# NucleoShield.net
KiCad netlist of a schematic drawn in EAGLE
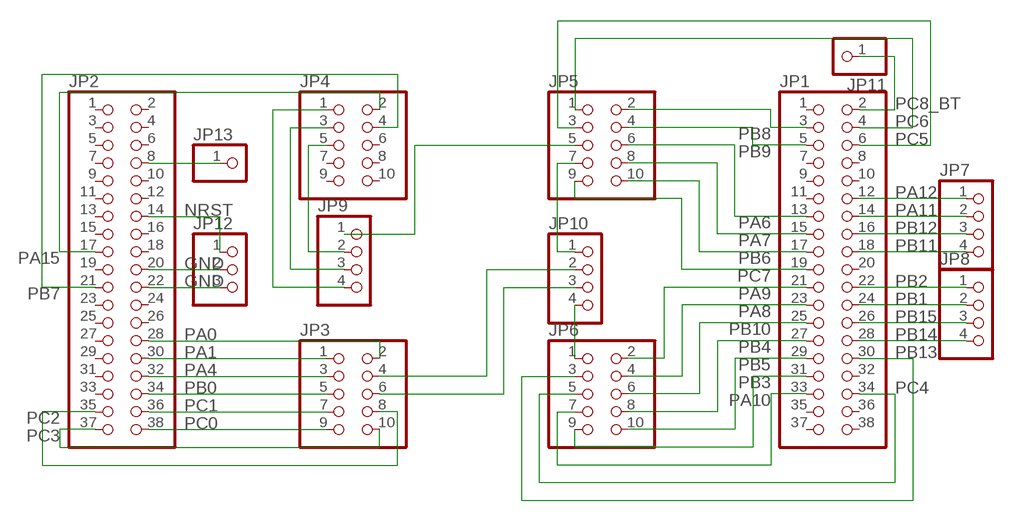
[diagram p0: schematic, sheet 1]

(export (version "E")
  (design (tool "Eeschema 10.0.6"))
  (components
    (comp (ref "JP1")
      (value "PINHD-2X19")
      (footprint "eagle-import:2X19")
      (libsource (lib "eagle-import") (part "PINHD-2X19"))
    )
    (comp (ref "JP2")
      (value "PINHD-2X19")
      (footprint "eagle-import:2X19")
      (libsource (lib "eagle-import") (part "PINHD-2X19"))
    )
    (comp (ref "JP3")
      (value "PINHD-2X5")
      (footprint "eagle-import:2X05")
      (libsource (lib "eagle-import") (part "PINHD-2X5"))
    )
    (comp (ref "JP4")
      (value "PINHD-2X5")
      (footprint "eagle-import:2X05")
      (libsource (lib "eagle-import") (part "PINHD-2X5"))
    )
    (comp (ref "JP5")
      (value "PINHD-2X5")
      (footprint "eagle-import:2X05")
      (libsource (lib "eagle-import") (part "PINHD-2X5"))
    )
    (comp (ref "JP6")
      (value "PINHD-2X5")
      (footprint "eagle-import:2X05")
      (libsource (lib "eagle-import") (part "PINHD-2X5"))
    )
    (comp (ref "JP7")
      (value "PINHD-1X4")
      (footprint "eagle-import:1X04")
      (libsource (lib "eagle-import") (part "PINHD-1X4"))
    )
    (comp (ref "JP8")
      (value "PINHD-1X4")
      (footprint "eagle-import:1X04")
      (libsource (lib "eagle-import") (part "PINHD-1X4"))
    )
    (comp (ref "JP9")
      (value "PINHD-1X4")
      (footprint "eagle-import:1X04")
      (libsource (lib "eagle-import") (part "PINHD-1X4"))
    )
    (comp (ref "JP10")
      (value "PINHD-1X4")
      (footprint "eagle-import:1X04")
      (libsource (lib "eagle-import") (part "PINHD-1X4"))
    )
    (comp (ref "JP11")
      (value "PINHD-1X1")
      (footprint "eagle-import:1X01")
      (libsource (lib "eagle-import") (part "PINHD-1X1"))
    )
    (comp (ref "JP12")
      (value "PINHD-1X3")
      (footprint "eagle-import:1X03")
      (libsource (lib "eagle-import") (part "PINHD-1X3"))
    )
    (comp (ref "JP13")
      (value "PINHD-1X1")
      (footprint "eagle-import:1X01")
      (libsource (lib "eagle-import") (part "PINHD-1X1"))
    )
  )
  (nets
    (net (code "1") (name "/GND") (class "Default")
      (node (ref "JP12") (pin "2") (pinfunction "2_2") (pintype "passive"))
      (node (ref "JP12") (pin "3") (pinfunction "3_3") (pintype "passive"))
      (node (ref "JP2") (pin "20") (pinfunction "20_20") (pintype "passive"))
      (node (ref "JP2") (pin "22") (pinfunction "22_22") (pintype "passive"))
    )
    (net (code "2") (name "/NRST") (class "Default")
      (node (ref "JP12") (pin "1") (pinfunction "1_1") (pintype "passive"))
      (node (ref "JP2") (pin "14") (pinfunction "14_14") (pintype "passive"))
    )
    (net (code "3") (name "/PA0") (class "Default")
      (node (ref "JP2") (pin "28") (pinfunction "28_28") (pintype "passive"))
      (node (ref "JP3") (pin "2") (pinfunction "2_2") (pintype "passive"))
    )
    (net (code "4") (name "/PA1") (class "Default")
      (node (ref "JP2") (pin "30") (pinfunction "30_30") (pintype "passive"))
      (node (ref "JP3") (pin "1") (pinfunction "1_1") (pintype "passive"))
    )
    (net (code "5") (name "/PA4") (class "Default")
      (node (ref "JP2") (pin "32") (pinfunction "32_32") (pintype "passive"))
      (node (ref "JP3") (pin "3") (pinfunction "3_3") (pintype "passive"))
    )
    (net (code "6") (name "/PA6") (class "Default")
      (node (ref "JP1") (pin "13") (pinfunction "13_13") (pintype "passive"))
      (node (ref "JP5") (pin "6") (pinfunction "6_6") (pintype "passive"))
    )
    (net (code "7") (name "/PA7") (class "Default")
      (node (ref "JP1") (pin "15") (pinfunction "15_15") (pintype "passive"))
      (node (ref "JP5") (pin "8") (pinfunction "8_8") (pintype "passive"))
    )
    (net (code "8") (name "/PA8") (class "Default")
      (node (ref "JP1") (pin "23") (pinfunction "23_23") (pintype "passive"))
      (node (ref "JP6") (pin "4") (pinfunction "4_4") (pintype "passive"))
    )
    (net (code "9") (name "/PA9") (class "Default")
      (node (ref "JP1") (pin "21") (pinfunction "21_21") (pintype "passive"))
      (node (ref "JP6") (pin "2") (pinfunction "2_2") (pintype "passive"))
    )
    (net (code "10") (name "/PA10") (class "Default")
      (node (ref "JP1") (pin "33") (pinfunction "33_33") (pintype "passive"))
      (node (ref "JP6") (pin "7") (pinfunction "7_7") (pintype "passive"))
    )
    (net (code "11") (name "/PA11") (class "Default")
      (node (ref "JP1") (pin "14") (pinfunction "14_14") (pintype "passive"))
      (node (ref "JP7") (pin "2") (pinfunction "2_2") (pintype "passive"))
    )
    (net (code "12") (name "/PA12") (class "Default")
      (node (ref "JP1") (pin "12") (pinfunction "12_12") (pintype "passive"))
      (node (ref "JP7") (pin "1") (pinfunction "1_1") (pintype "passive"))
    )
    (net (code "13") (name "/PA15") (class "Default")
      (node (ref "JP2") (pin "17") (pinfunction "17_17") (pintype "passive"))
      (node (ref "JP4") (pin "2") (pinfunction "2_2") (pintype "passive"))
    )
    (net (code "14") (name "/PB0") (class "Default")
      (node (ref "JP2") (pin "34") (pinfunction "34_34") (pintype "passive"))
      (node (ref "JP3") (pin "5") (pinfunction "5_5") (pintype "passive"))
    )
    (net (code "15") (name "/PB1") (class "Default")
      (node (ref "JP1") (pin "24") (pinfunction "24_24") (pintype "passive"))
      (node (ref "JP8") (pin "2") (pinfunction "2_2") (pintype "passive"))
    )
    (net (code "16") (name "/PB2") (class "Default")
      (node (ref "JP1") (pin "22") (pinfunction "22_22") (pintype "passive"))
      (node (ref "JP8") (pin "1") (pinfunction "1_1") (pintype "passive"))
    )
    (net (code "17") (name "/PB3") (class "Default")
      (node (ref "JP1") (pin "31") (pinfunction "31_31") (pintype "passive"))
      (node (ref "JP6") (pin "9") (pinfunction "9_9") (pintype "passive"))
    )
    (net (code "18") (name "/PB4") (class "Default")
      (node (ref "JP1") (pin "27") (pinfunction "27_27") (pintype "passive"))
      (node (ref "JP6") (pin "8") (pinfunction "8_8") (pintype "passive"))
    )
    (net (code "19") (name "/PB5") (class "Default")
      (node (ref "JP1") (pin "29") (pinfunction "29_29") (pintype "passive"))
      (node (ref "JP6") (pin "10") (pinfunction "10_10") (pintype "passive"))
    )
    (net (code "20") (name "/PB6") (class "Default")
      (node (ref "JP1") (pin "17") (pinfunction "17_17") (pintype "passive"))
      (node (ref "JP5") (pin "10") (pinfunction "10_10") (pintype "passive"))
    )
    (net (code "21") (name "/PB7") (class "Default")
      (node (ref "JP2") (pin "21") (pinfunction "21_21") (pintype "passive"))
      (node (ref "JP4") (pin "4") (pinfunction "4_4") (pintype "passive"))
    )
    (net (code "22") (name "/PB8") (class "Default")
      (node (ref "JP1") (pin "3") (pinfunction "3_3") (pintype "passive"))
      (node (ref "JP5") (pin "2") (pinfunction "2_2") (pintype "passive"))
    )
    (net (code "23") (name "/PB9") (class "Default")
      (node (ref "JP1") (pin "5") (pinfunction "5_5") (pintype "passive"))
      (node (ref "JP5") (pin "4") (pinfunction "4_4") (pintype "passive"))
    )
    (net (code "24") (name "/PB10") (class "Default")
      (node (ref "JP1") (pin "25") (pinfunction "25_25") (pintype "passive"))
      (node (ref "JP6") (pin "6") (pinfunction "6_6") (pintype "passive"))
    )
    (net (code "25") (name "/PB11") (class "Default")
      (node (ref "JP1") (pin "18") (pinfunction "18_18") (pintype "passive"))
      (node (ref "JP7") (pin "4") (pinfunction "4_4") (pintype "passive"))
    )
    (net (code "26") (name "/PB12") (class "Default")
      (node (ref "JP1") (pin "16") (pinfunction "16_16") (pintype "passive"))
      (node (ref "JP7") (pin "3") (pinfunction "3_3") (pintype "passive"))
    )
    (net (code "27") (name "/PB13") (class "Default")
      (node (ref "JP1") (pin "30") (pinfunction "30_30") (pintype "passive"))
      (node (ref "JP6") (pin "3") (pinfunction "3_3") (pintype "passive"))
    )
    (net (code "28") (name "/PB14") (class "Default")
      (node (ref "JP1") (pin "28") (pinfunction "28_28") (pintype "passive"))
      (node (ref "JP8") (pin "4") (pinfunction "4_4") (pintype "passive"))
    )
    (net (code "29") (name "/PB15") (class "Default")
      (node (ref "JP1") (pin "26") (pinfunction "26_26") (pintype "passive"))
      (node (ref "JP8") (pin "3") (pinfunction "3_3") (pintype "passive"))
    )
    (net (code "30") (name "/PC0") (class "Default")
      (node (ref "JP2") (pin "38") (pinfunction "38_38") (pintype "passive"))
      (node (ref "JP3") (pin "9") (pinfunction "9_9") (pintype "passive"))
    )
    (net (code "31") (name "/PC1") (class "Default")
      (node (ref "JP2") (pin "36") (pinfunction "36_36") (pintype "passive"))
      (node (ref "JP3") (pin "7") (pinfunction "7_7") (pintype "passive"))
    )
    (net (code "32") (name "/PC2") (class "Default")
      (node (ref "JP2") (pin "35") (pinfunction "35_35") (pintype "passive"))
      (node (ref "JP3") (pin "8") (pinfunction "8_8") (pintype "passive"))
    )
    (net (code "33") (name "/PC3") (class "Default")
      (node (ref "JP2") (pin "37") (pinfunction "37_37") (pintype "passive"))
      (node (ref "JP3") (pin "10") (pinfunction "10_10") (pintype "passive"))
    )
    (net (code "34") (name "/PC4") (class "Default")
      (node (ref "JP1") (pin "34") (pinfunction "34_34") (pintype "passive"))
      (node (ref "JP6") (pin "5") (pinfunction "5_5") (pintype "passive"))
    )
    (net (code "35") (name "/PC5") (class "Default")
      (node (ref "JP1") (pin "6") (pinfunction "6_6") (pintype "passive"))
      (node (ref "JP5") (pin "3") (pinfunction "3_3") (pintype "passive"))
    )
    (net (code "36") (name "/PC6") (class "Default")
      (node (ref "JP1") (pin "4") (pinfunction "4_4") (pintype "passive"))
      (node (ref "JP5") (pin "1") (pinfunction "1_1") (pintype "passive"))
    )
    (net (code "37") (name "/PC7") (class "Default")
      (node (ref "JP1") (pin "19") (pinfunction "19_19") (pintype "passive"))
      (node (ref "JP5") (pin "9") (pinfunction "9_9") (pintype "passive"))
    )
    (net (code "38") (name "/PC8_BT") (class "Default")
      (node (ref "JP1") (pin "2") (pinfunction "2_2") (pintype "passive"))
      (node (ref "JP11") (pin "1") (pinfunction "1_1") (pintype "passive"))
    )
    (net (code "39") (name "Net-(JP4-Pad1)") (class "Default")
      (node (ref "JP4") (pin "1") (pinfunction "1_1") (pintype "passive"))
      (node (ref "JP9") (pin "4") (pinfunction "4_4") (pintype "passive"))
    )
    (net (code "40") (name "Net-(JP4-Pad3)") (class "Default")
      (node (ref "JP4") (pin "3") (pinfunction "3_3") (pintype "passive"))
      (node (ref "JP9") (pin "3") (pinfunction "3_3") (pintype "passive"))
    )
    (net (code "41") (name "Net-(JP4-Pad5)") (class "Default")
      (node (ref "JP4") (pin "5") (pinfunction "5_5") (pintype "passive"))
      (node (ref "JP9") (pin "2") (pinfunction "2_2") (pintype "passive"))
    )
    (net (code "42") (name "Net-(JP5-Pad5)") (class "Default")
      (node (ref "JP5") (pin "5") (pinfunction "5_5") (pintype "passive"))
      (node (ref "JP9") (pin "1") (pinfunction "1_1") (pintype "passive"))
    )
    (net (code "43") (name "Net-(JP10-Pad1)") (class "Default")
      (node (ref "JP10") (pin "1") (pinfunction "1_1") (pintype "passive"))
      (node (ref "JP5") (pin "7") (pinfunction "7_7") (pintype "passive"))
    )
    (net (code "44") (name "Net-(JP10-Pad2)") (class "Default")
      (node (ref "JP10") (pin "2") (pinfunction "2_2") (pintype "passive"))
      (node (ref "JP3") (pin "4") (pinfunction "4_4") (pintype "passive"))
    )
    (net (code "45") (name "Net-(JP10-Pad3)") (class "Default")
      (node (ref "JP10") (pin "3") (pinfunction "3_3") (pintype "passive"))
      (node (ref "JP3") (pin "6") (pinfunction "6_6") (pintype "passive"))
    )
    (net (code "46") (name "Net-(JP10-Pad4)") (class "Default")
      (node (ref "JP10") (pin "4") (pinfunction "4_4") (pintype "passive"))
      (node (ref "JP6") (pin "1") (pinfunction "1_1") (pintype "passive"))
    )
    (net (code "47") (name "Net-(JP13-Pad1)") (class "Default")
      (node (ref "JP13") (pin "1") (pinfunction "1_1") (pintype "passive"))
      (node (ref "JP2") (pin "8") (pinfunction "8_8") (pintype "passive"))
    )
    (net (code "48") (name "unconnected-(JP1-Pad1)") (class "Default")
      (node (ref "JP1") (pin "1") (pinfunction "1_1") (pintype "passive"))
    )
    (net (code "49") (name "unconnected-(JP1-Pad7)") (class "Default")
      (node (ref "JP1") (pin "7") (pinfunction "7_7") (pintype "passive"))
    )
    (net (code "50") (name "unconnected-(JP1-Pad8)") (class "Default")
      (node (ref "JP1") (pin "8") (pinfunction "8_8") (pintype "passive"))
    )
    (net (code "51") (name "unconnected-(JP1-Pad9)") (class "Default")
      (node (ref "JP1") (pin "9") (pinfunction "9_9") (pintype "passive"))
    )
    (net (code "52") (name "unconnected-(JP1-Pad10)") (class "Default")
      (node (ref "JP1") (pin "10") (pinfunction "10_10") (pintype "passive"))
    )
    (net (code "53") (name "unconnected-(JP1-Pad11)") (class "Default")
      (node (ref "JP1") (pin "11") (pinfunction "11_11") (pintype "passive"))
    )
    (net (code "54") (name "unconnected-(JP1-Pad20)") (class "Default")
      (node (ref "JP1") (pin "20") (pinfunction "20_20") (pintype "passive"))
    )
    (net (code "55") (name "unconnected-(JP1-Pad32)") (class "Default")
      (node (ref "JP1") (pin "32") (pinfunction "32_32") (pintype "passive"))
    )
    (net (code "56") (name "unconnected-(JP1-Pad35)") (class "Default")
      (node (ref "JP1") (pin "35") (pinfunction "35_35") (pintype "passive"))
    )
    (net (code "57") (name "unconnected-(JP1-Pad36)") (class "Default")
      (node (ref "JP1") (pin "36") (pinfunction "36_36") (pintype "passive"))
    )
    (net (code "58") (name "unconnected-(JP1-Pad37)") (class "Default")
      (node (ref "JP1") (pin "37") (pinfunction "37_37") (pintype "passive"))
    )
    (net (code "59") (name "unconnected-(JP1-Pad38)") (class "Default")
      (node (ref "JP1") (pin "38") (pinfunction "38_38") (pintype "passive"))
    )
    (net (code "60") (name "unconnected-(JP2-Pad1)") (class "Default")
      (node (ref "JP2") (pin "1") (pinfunction "1_1") (pintype "passive"))
    )
    (net (code "61") (name "unconnected-(JP2-Pad2)") (class "Default")
      (node (ref "JP2") (pin "2") (pinfunction "2_2") (pintype "passive"))
    )
    (net (code "62") (name "unconnected-(JP2-Pad3)") (class "Default")
      (node (ref "JP2") (pin "3") (pinfunction "3_3") (pintype "passive"))
    )
    (net (code "63") (name "unconnected-(JP2-Pad4)") (class "Default")
      (node (ref "JP2") (pin "4") (pinfunction "4_4") (pintype "passive"))
    )
    (net (code "64") (name "unconnected-(JP2-Pad5)") (class "Default")
      (node (ref "JP2") (pin "5") (pinfunction "5_5") (pintype "passive"))
    )
    (net (code "65") (name "unconnected-(JP2-Pad6)") (class "Default")
      (node (ref "JP2") (pin "6") (pinfunction "6_6") (pintype "passive"))
    )
    (net (code "66") (name "unconnected-(JP2-Pad7)") (class "Default")
      (node (ref "JP2") (pin "7") (pinfunction "7_7") (pintype "passive"))
    )
    (net (code "67") (name "unconnected-(JP2-Pad9)") (class "Default")
      (node (ref "JP2") (pin "9") (pinfunction "9_9") (pintype "passive"))
    )
    (net (code "68") (name "unconnected-(JP2-Pad10)") (class "Default")
      (node (ref "JP2") (pin "10") (pinfunction "10_10") (pintype "passive"))
    )
    (net (code "69") (name "unconnected-(JP2-Pad11)") (class "Default")
      (node (ref "JP2") (pin "11") (pinfunction "11_11") (pintype "passive"))
    )
    (net (code "70") (name "unconnected-(JP2-Pad12)") (class "Default")
      (node (ref "JP2") (pin "12") (pinfunction "12_12") (pintype "passive"))
    )
    (net (code "71") (name "unconnected-(JP2-Pad13)") (class "Default")
      (node (ref "JP2") (pin "13") (pinfunction "13_13") (pintype "passive"))
    )
    (net (code "72") (name "unconnected-(JP2-Pad15)") (class "Default")
      (node (ref "JP2") (pin "15") (pinfunction "15_15") (pintype "passive"))
    )
    (net (code "73") (name "unconnected-(JP2-Pad16)") (class "Default")
      (node (ref "JP2") (pin "16") (pinfunction "16_16") (pintype "passive"))
    )
    (net (code "74") (name "unconnected-(JP2-Pad18)") (class "Default")
      (node (ref "JP2") (pin "18") (pinfunction "18_18") (pintype "passive"))
    )
    (net (code "75") (name "unconnected-(JP2-Pad19)") (class "Default")
      (node (ref "JP2") (pin "19") (pinfunction "19_19") (pintype "passive"))
    )
    (net (code "76") (name "unconnected-(JP2-Pad23)") (class "Default")
      (node (ref "JP2") (pin "23") (pinfunction "23_23") (pintype "passive"))
    )
    (net (code "77") (name "unconnected-(JP2-Pad24)") (class "Default")
      (node (ref "JP2") (pin "24") (pinfunction "24_24") (pintype "passive"))
    )
    (net (code "78") (name "unconnected-(JP2-Pad25)") (class "Default")
      (node (ref "JP2") (pin "25") (pinfunction "25_25") (pintype "passive"))
    )
    (net (code "79") (name "unconnected-(JP2-Pad26)") (class "Default")
      (node (ref "JP2") (pin "26") (pinfunction "26_26") (pintype "passive"))
    )
    (net (code "80") (name "unconnected-(JP2-Pad27)") (class "Default")
      (node (ref "JP2") (pin "27") (pinfunction "27_27") (pintype "passive"))
    )
    (net (code "81") (name "unconnected-(JP2-Pad29)") (class "Default")
      (node (ref "JP2") (pin "29") (pinfunction "29_29") (pintype "passive"))
    )
    (net (code "82") (name "unconnected-(JP2-Pad31)") (class "Default")
      (node (ref "JP2") (pin "31") (pinfunction "31_31") (pintype "passive"))
    )
    (net (code "83") (name "unconnected-(JP2-Pad33)") (class "Default")
      (node (ref "JP2") (pin "33") (pinfunction "33_33") (pintype "passive"))
    )
    (net (code "84") (name "unconnected-(JP4-Pad6)") (class "Default")
      (node (ref "JP4") (pin "6") (pinfunction "6_6") (pintype "passive"))
    )
    (net (code "85") (name "unconnected-(JP4-Pad7)") (class "Default")
      (node (ref "JP4") (pin "7") (pinfunction "7_7") (pintype "passive"))
    )
    (net (code "86") (name "unconnected-(JP4-Pad8)") (class "Default")
      (node (ref "JP4") (pin "8") (pinfunction "8_8") (pintype "passive"))
    )
    (net (code "87") (name "unconnected-(JP4-Pad9)") (class "Default")
      (node (ref "JP4") (pin "9") (pinfunction "9_9") (pintype "passive"))
    )
    (net (code "88") (name "unconnected-(JP4-Pad10)") (class "Default")
      (node (ref "JP4") (pin "10") (pinfunction "10_10") (pintype "passive"))
    )
  )
)
